# IO.net
KiCad netlist of a schematic drawn in Altium Designer
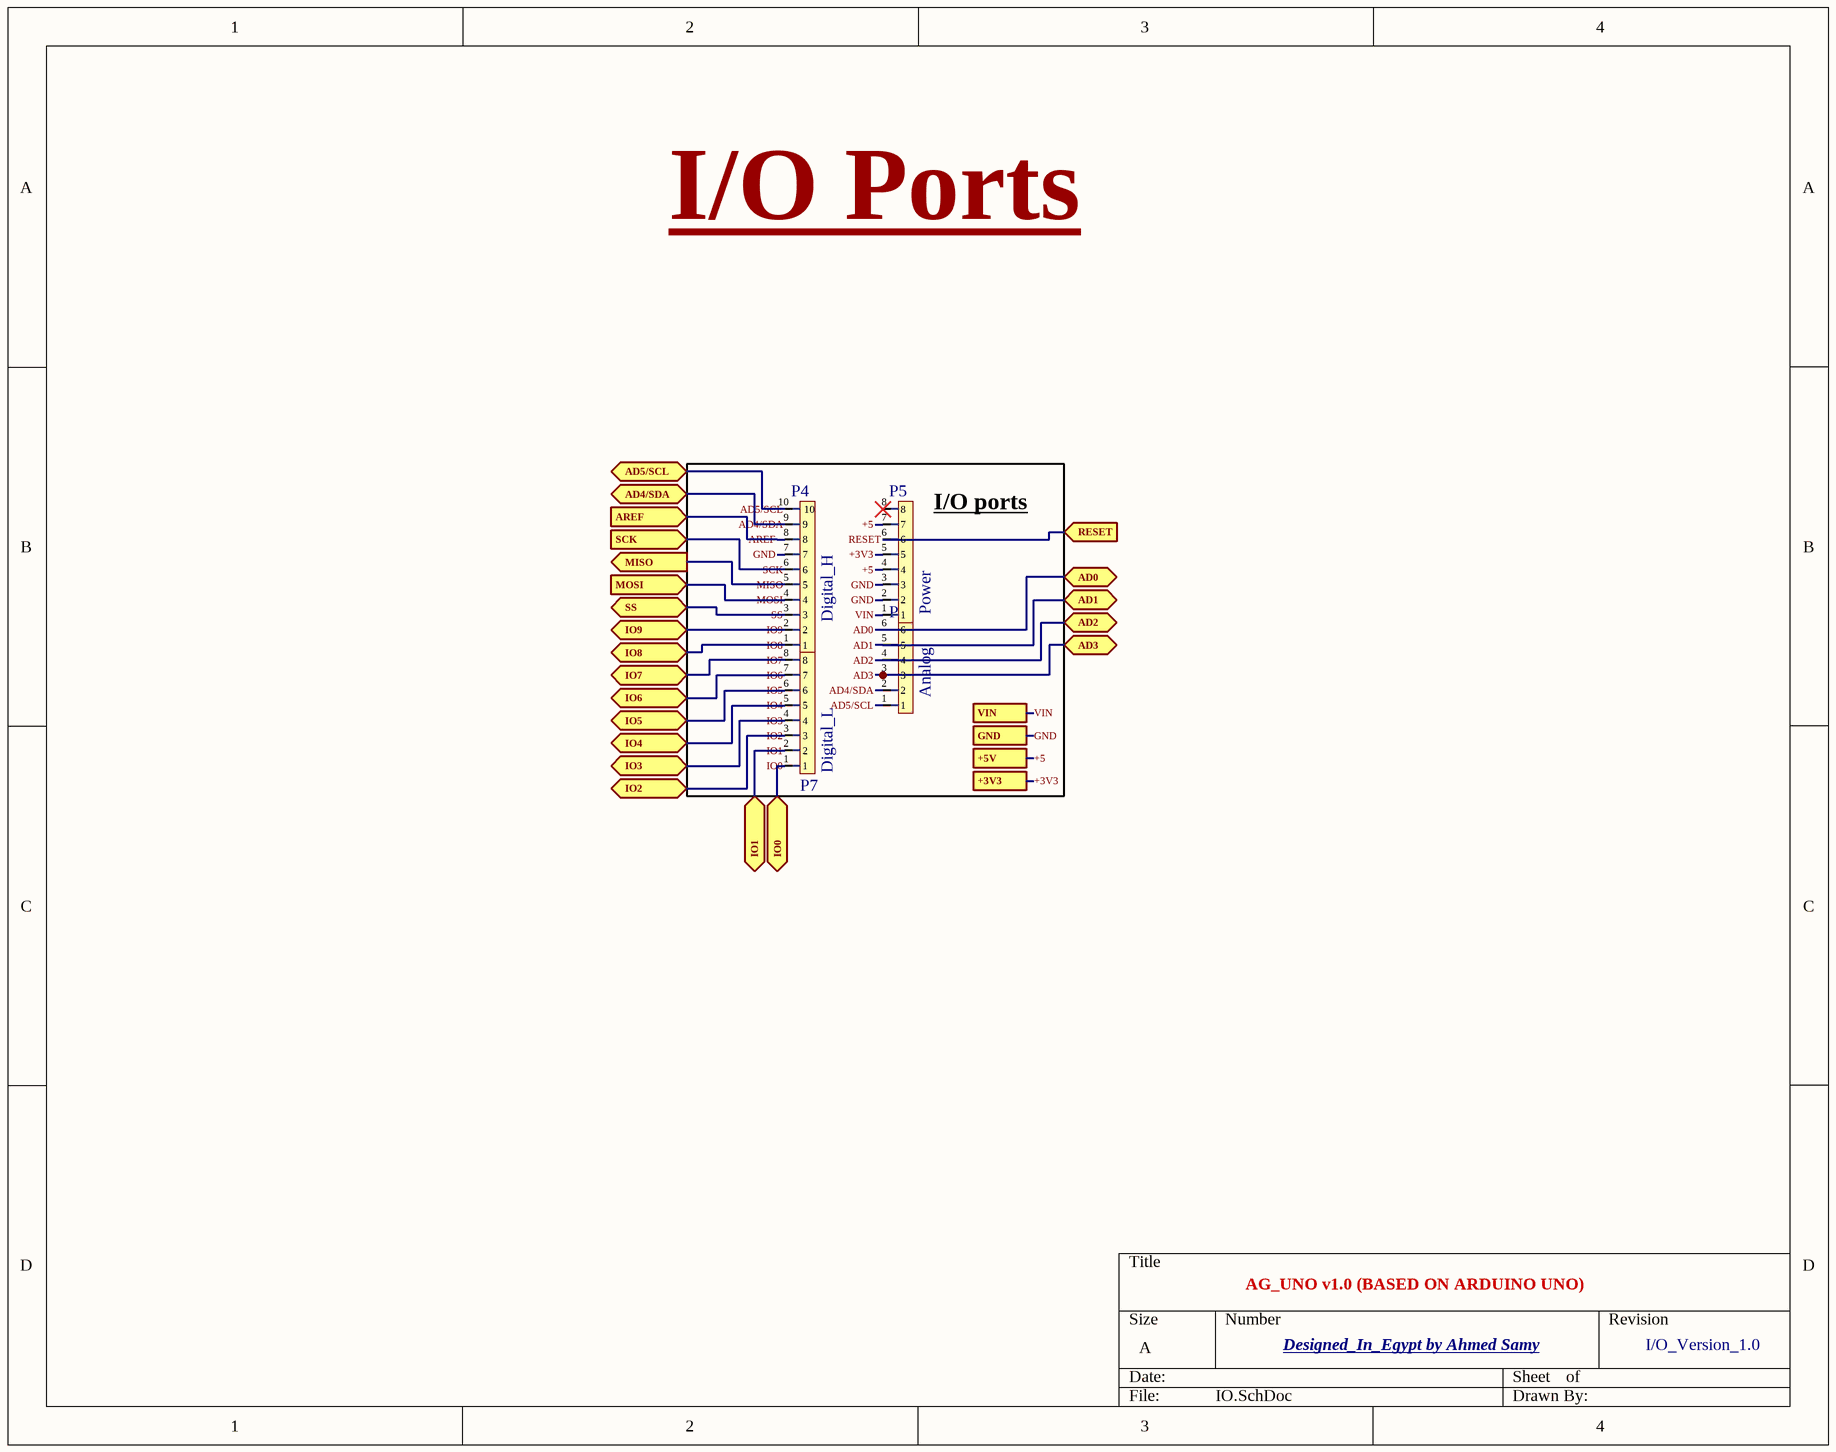
[diagram p0: IO.SchDoc]

(export (version "E")
  (design (tool "Eeschema 10.0.6"))
  (components
    (comp (ref "P4")
      (value "Digital_H")
      (footprint "NPPN101BFCN-RC")
      (description "10 Position Header Connector 0.079\" (2.00mm) Through Hole Gold")
      (libsource (lib "Task") (part "NPPN101BFCN-RC"))
    )
    (comp (ref "P5")
      (value "Power")
      (footprint "PPTC081LFBN-RC")
      (description "8 Position Header Connector 0.100\" (2.54mm) Through Hole Tin")
      (libsource (lib "Task") (part "PPTC081LFBN-RC"))
    )
    (comp (ref "P6")
      (value "Analog")
      (footprint "PPTC061LFBN-RC")
      (description "6 Position Female Pin Header Connector 0.100\" (2.54mm) Through Hole Tin")
      (libsource (lib "Task") (part "PPTC061LFBN-RC"))
    )
    (comp (ref "P7")
      (value "Digital_L")
      (footprint "PPTC081LFBN-RC")
      (description "8 Position Header Connector 0.100\" (2.54mm) Through Hole Tin")
      (libsource (lib "Task") (part "PPTC081LFBN-RC"))
    )
  )
  (nets
    (net (code "1") (name "/+3V3") (class "Default")
      (node (ref "P5") (pin "5") (pinfunction "5_5") (pintype "passive"))
    )
    (net (code "2") (name "/+5") (class "Default")
      (node (ref "P5") (pin "4") (pinfunction "4_4") (pintype "passive"))
      (node (ref "P5") (pin "7") (pinfunction "7_7") (pintype "passive"))
    )
    (net (code "3") (name "/AD0") (class "Default")
      (node (ref "P6") (pin "6") (pinfunction "6_6") (pintype "passive"))
    )
    (net (code "4") (name "/AD1") (class "Default")
      (node (ref "P6") (pin "5") (pinfunction "5_5") (pintype "passive"))
    )
    (net (code "5") (name "/AD2") (class "Default")
      (node (ref "P6") (pin "4") (pinfunction "4_4") (pintype "passive"))
    )
    (net (code "6") (name "/AD3") (class "Default")
      (node (ref "P6") (pin "3") (pinfunction "3_3") (pintype "passive"))
    )
    (net (code "7") (name "/AD4{slash}SDA") (class "Default")
      (node (ref "P4") (pin "9") (pinfunction "9_9") (pintype "passive"))
      (node (ref "P6") (pin "2") (pinfunction "2_2") (pintype "passive"))
    )
    (net (code "8") (name "/AD5{slash}SCL") (class "Default")
      (node (ref "P4") (pin "10") (pinfunction "10_10") (pintype "passive"))
      (node (ref "P6") (pin "1") (pinfunction "1_1") (pintype "passive"))
    )
    (net (code "9") (name "/AREF") (class "Default")
      (node (ref "P4") (pin "8") (pinfunction "8_8") (pintype "passive"))
    )
    (net (code "10") (name "/GND") (class "Default")
      (node (ref "P4") (pin "7") (pinfunction "7_7") (pintype "passive"))
      (node (ref "P5") (pin "2") (pinfunction "2_2") (pintype "passive"))
      (node (ref "P5") (pin "3") (pinfunction "3_3") (pintype "passive"))
    )
    (net (code "11") (name "/IO0") (class "Default")
      (node (ref "P7") (pin "1") (pinfunction "1_1") (pintype "passive"))
    )
    (net (code "12") (name "/IO1") (class "Default")
      (node (ref "P7") (pin "2") (pinfunction "2_2") (pintype "passive"))
    )
    (net (code "13") (name "/IO2") (class "Default")
      (node (ref "P7") (pin "3") (pinfunction "3_3") (pintype "passive"))
    )
    (net (code "14") (name "/IO3") (class "Default")
      (node (ref "P7") (pin "4") (pinfunction "4_4") (pintype "passive"))
    )
    (net (code "15") (name "/IO4") (class "Default")
      (node (ref "P7") (pin "5") (pinfunction "5_5") (pintype "passive"))
    )
    (net (code "16") (name "/IO5") (class "Default")
      (node (ref "P7") (pin "6") (pinfunction "6_6") (pintype "passive"))
    )
    (net (code "17") (name "/IO6") (class "Default")
      (node (ref "P7") (pin "7") (pinfunction "7_7") (pintype "passive"))
    )
    (net (code "18") (name "/IO7") (class "Default")
      (node (ref "P7") (pin "8") (pinfunction "8_8") (pintype "passive"))
    )
    (net (code "19") (name "/IO8") (class "Default")
      (node (ref "P4") (pin "1") (pinfunction "1_1") (pintype "passive"))
    )
    (net (code "20") (name "/IO9") (class "Default")
      (node (ref "P4") (pin "2") (pinfunction "2_2") (pintype "passive"))
    )
    (net (code "21") (name "/MISO") (class "Default")
      (node (ref "P4") (pin "5") (pinfunction "5_5") (pintype "passive"))
    )
    (net (code "22") (name "/MOSI") (class "Default")
      (node (ref "P4") (pin "4") (pinfunction "4_4") (pintype "passive"))
    )
    (net (code "23") (name "/RESET") (class "Default")
      (node (ref "P5") (pin "6") (pinfunction "6_6") (pintype "passive"))
    )
    (net (code "24") (name "/SCK") (class "Default")
      (node (ref "P4") (pin "6") (pinfunction "6_6") (pintype "passive"))
    )
    (net (code "25") (name "/SS") (class "Default")
      (node (ref "P4") (pin "3") (pinfunction "3_3") (pintype "passive"))
    )
    (net (code "26") (name "/VIN") (class "Default")
      (node (ref "P5") (pin "1") (pinfunction "1_1") (pintype "passive"))
    )
    (net (code "27") (name "unconnected-(P5-Pad8)") (class "Default")
      (node (ref "P5") (pin "8") (pinfunction "8_8") (pintype "passive+no_connect"))
    )
  )
)
